# CVx1.net
KiCad netlist of a schematic drawn in Altium Designer
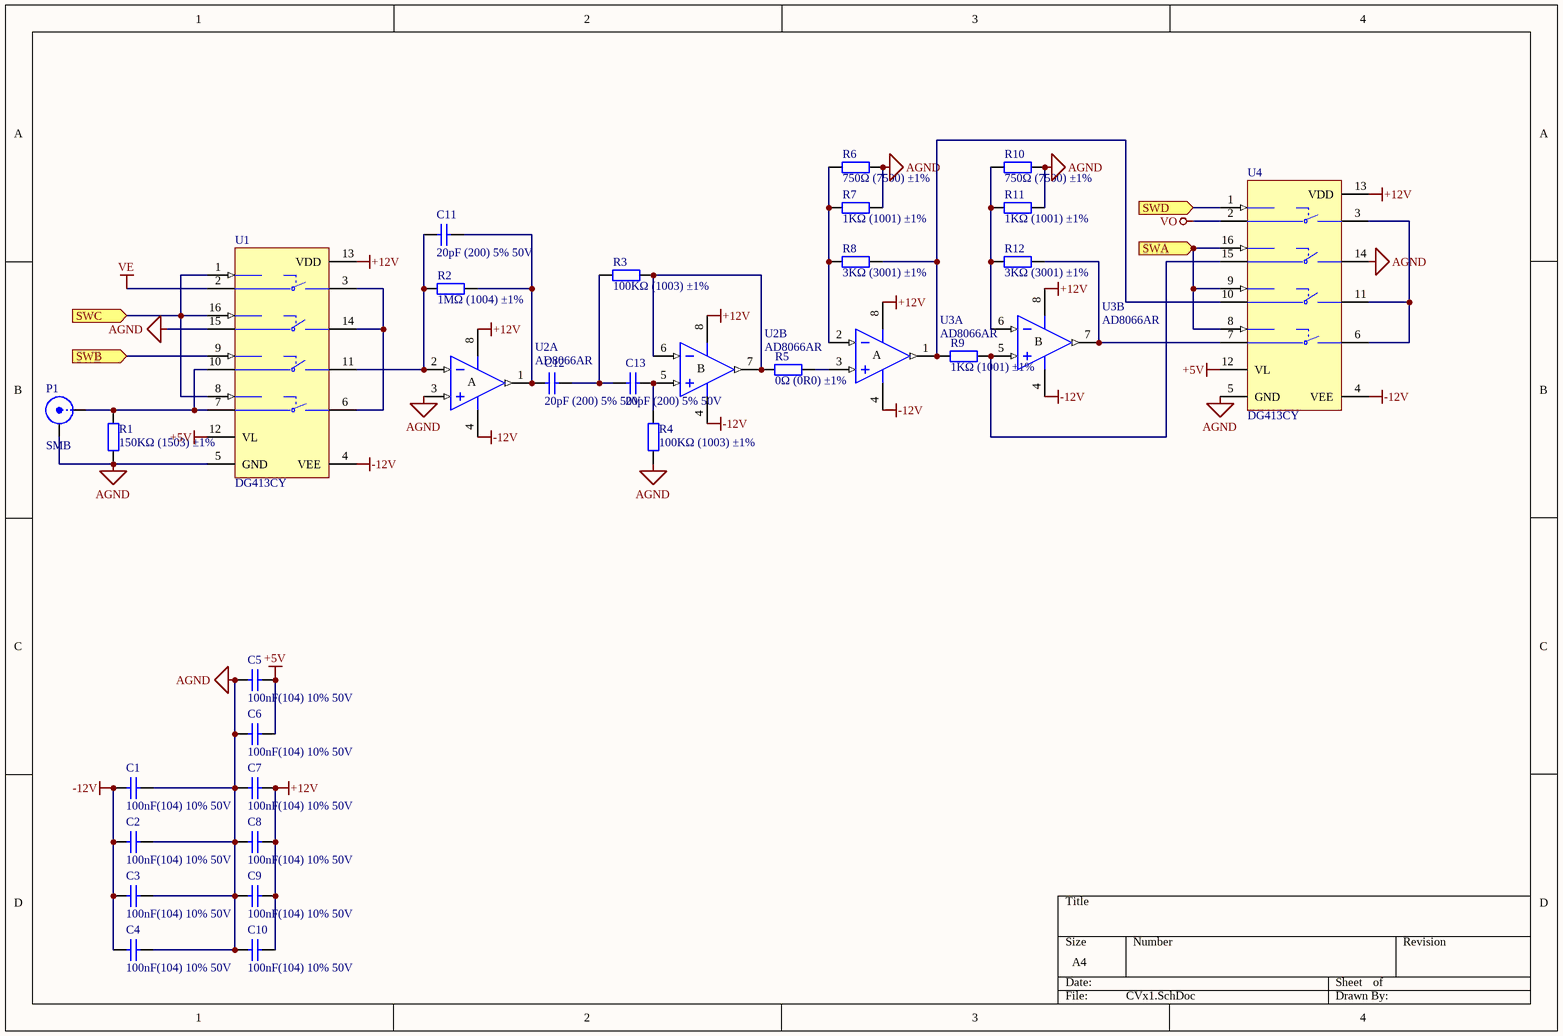
[diagram p0: CVx1.SchDoc]

(export (version "E")
  (design (tool "Eeschema 10.0.6"))
  (components
    (comp (ref "C1")
      (value "100nF(104) 10% 50V")
      (footprint "LC-0805_C")
      (description "贴片电容")
      (libsource (lib "Miscellaneous Devices LC") (part "0805 100nF(104) 10% 50V"))
    )
    (comp (ref "C2")
      (value "100nF(104) 10% 50V")
      (footprint "LC-0805_C")
      (description "贴片电容")
      (libsource (lib "Miscellaneous Devices LC") (part "0805 100nF(104) 10% 50V"))
    )
    (comp (ref "C3")
      (value "100nF(104) 10% 50V")
      (footprint "LC-0805_C")
      (description "贴片电容")
      (libsource (lib "Miscellaneous Devices LC") (part "0805 100nF(104) 10% 50V"))
    )
    (comp (ref "C4")
      (value "100nF(104) 10% 50V")
      (footprint "LC-0805_C")
      (description "贴片电容")
      (libsource (lib "Miscellaneous Devices LC") (part "0805 100nF(104) 10% 50V"))
    )
    (comp (ref "C5")
      (value "100nF(104) 10% 50V")
      (footprint "LC-0805_C")
      (description "贴片电容")
      (libsource (lib "Miscellaneous Devices LC") (part "0805 100nF(104) 10% 50V"))
    )
    (comp (ref "C6")
      (value "100nF(104) 10% 50V")
      (footprint "LC-0805_C")
      (description "贴片电容")
      (libsource (lib "Miscellaneous Devices LC") (part "0805 100nF(104) 10% 50V"))
    )
    (comp (ref "C7")
      (value "100nF(104) 10% 50V")
      (footprint "LC-0805_C")
      (description "贴片电容")
      (libsource (lib "Miscellaneous Devices LC") (part "0805 100nF(104) 10% 50V"))
    )
    (comp (ref "C8")
      (value "100nF(104) 10% 50V")
      (footprint "LC-0805_C")
      (description "贴片电容")
      (libsource (lib "Miscellaneous Devices LC") (part "0805 100nF(104) 10% 50V"))
    )
    (comp (ref "C9")
      (value "100nF(104) 10% 50V")
      (footprint "LC-0805_C")
      (description "贴片电容")
      (libsource (lib "Miscellaneous Devices LC") (part "0805 100nF(104) 10% 50V"))
    )
    (comp (ref "C10")
      (value "100nF(104) 10% 50V")
      (footprint "LC-0805_C")
      (description "贴片电容")
      (libsource (lib "Miscellaneous Devices LC") (part "0805 100nF(104) 10% 50V"))
    )
    (comp (ref "C11")
      (value "20pF (200) 5% 50V")
      (footprint "LC-0805_C")
      (description "贴片电容")
      (libsource (lib "Miscellaneous Devices LC") (part "0805 20pF (200) 5% 50V"))
    )
    (comp (ref "C12")
      (value "20pF (200) 5% 50V")
      (footprint "LC-0805_C")
      (description "贴片电容")
      (libsource (lib "Miscellaneous Devices LC") (part "0805 20pF (200) 5% 50V"))
    )
    (comp (ref "C13")
      (value "20pF (200) 5% 50V")
      (footprint "LC-0805_C")
      (description "贴片电容")
      (libsource (lib "Miscellaneous Devices LC") (part "0805 20pF (200) 5% 50V"))
    )
    (comp (ref "P1")
      (value "SMB")
      (footprint "SMB_V-RJ45")
      (description "SMB Straight Connector")
      (fields (field (name "PUBLISHER") "Altium Limited"))
      (libsource (lib "Miscellaneous Connectors") (part "SMB"))
    )
    (comp (ref "R1")
      (value "150KΩ (1503) ±1%")
      (footprint "LC-0805_R")
      (description "贴片电阻")
      (libsource (lib "Miscellaneous Devices LC") (part "0805 150KΩ (1503) 1%"))
    )
    (comp (ref "R2")
      (value "1MΩ (1004) ±1%")
      (footprint "LC-0805_R")
      (description "贴片电阻")
      (libsource (lib "Miscellaneous Devices LC") (part "0805 1MΩ (1004) 1%"))
    )
    (comp (ref "R3")
      (value "100KΩ (1003) ±1%")
      (footprint "LC-0805_R")
      (description "贴片电阻")
      (libsource (lib "Miscellaneous Devices LC") (part "0805 100KΩ (1003) 1%"))
    )
    (comp (ref "R4")
      (value "100KΩ (1003) ±1%")
      (footprint "LC-0805_R")
      (description "贴片电阻")
      (libsource (lib "") (part "0805 100KΩ (1003) 1%_1"))
    )
    (comp (ref "R5")
      (value "0Ω (0R0) ±1%")
      (footprint "LC-0805_R")
      (description "贴片电阻")
      (libsource (lib "Miscellaneous Devices LC") (part "0805 0Ω (0R0) 1%"))
    )
    (comp (ref "R6")
      (value "750Ω (7500) ±1%")
      (footprint "LC-0805_R")
      (description "贴片电阻")
      (libsource (lib "Miscellaneous Devices LC") (part "0805 750Ω (7500) 1%"))
    )
    (comp (ref "R7")
      (value "1KΩ (1001) ±1%")
      (footprint "LC-0805_R")
      (description "贴片电阻")
      (libsource (lib "Miscellaneous Devices LC") (part "0805 1KΩ (1001) 1%"))
    )
    (comp (ref "R8")
      (value "3KΩ (3001) ±1%")
      (footprint "LC-0805_R")
      (description "贴片电阻")
      (libsource (lib "Miscellaneous Devices LC") (part "0805 3KΩ (3001) 1%"))
    )
    (comp (ref "R9")
      (value "1KΩ (1001) ±1%")
      (footprint "LC-0805_R")
      (description "贴片电阻")
      (libsource (lib "Miscellaneous Devices LC") (part "0805 1KΩ (1001) 1%"))
    )
    (comp (ref "R10")
      (value "750Ω (7500) ±1%")
      (footprint "LC-0805_R")
      (description "贴片电阻")
      (libsource (lib "Miscellaneous Devices LC") (part "0805 750Ω (7500) 1%"))
    )
    (comp (ref "R11")
      (value "1KΩ (1001) ±1%")
      (footprint "LC-0805_R")
      (description "贴片电阻")
      (libsource (lib "Miscellaneous Devices LC") (part "0805 1KΩ (1001) 1%"))
    )
    (comp (ref "R12")
      (value "3KΩ (3001) ±1%")
      (footprint "LC-0805_R")
      (description "贴片电阻")
      (libsource (lib "Miscellaneous Devices LC") (part "0805 3KΩ (3001) 1%"))
    )
    (comp (ref "U1")
      (value "DG413CY")
      (footprint "NSO16_N")
      (description "Improved, Quad, SPST Analog Switches")
      (fields (field (name "PUBLISHER") "Altium Limited"))
      (libsource (lib "Maxim Logic Switch") (part "DG413CY"))
    )
    (comp (ref "U2")
      (value "AD8066AR")
      (footprint "SO-8_N")
      (description "Low Cost, 300MHz Voltage Feedback Amplifier")
      (fields (field (name "PUBLISHER") "Altium Limited"))
      (libsource (lib "AD Operational Amplifier") (part "AD8056AR"))
    )
    (comp (ref "U3")
      (value "AD8066AR")
      (footprint "SO-8_N")
      (description "Low Cost, 300MHz Voltage Feedback Amplifier")
      (fields (field (name "PUBLISHER") "Altium Limited"))
      (libsource (lib "AD Operational Amplifier") (part "AD8056AR"))
    )
    (comp (ref "U4")
      (value "DG413CY")
      (footprint "NSO16_N")
      (description "Improved, Quad, SPST Analog Switches")
      (fields (field (name "PUBLISHER") "Altium Limited"))
      (libsource (lib "Maxim Logic Switch") (part "DG413CY"))
    )
  )
  (nets
    (net (code "1") (name "+5V") (class "Default")
      (node (ref "C5") (pin "2") (pinfunction "2_2") (pintype "passive"))
      (node (ref "C6") (pin "2") (pinfunction "2_2") (pintype "passive"))
      (node (ref "U1") (pin "12") (pinfunction "VL_12") (pintype "power_in"))
      (node (ref "U4") (pin "12") (pinfunction "VL_12") (pintype "power_in"))
    )
    (net (code "2") (name "+12V") (class "Default")
      (node (ref "C10") (pin "2") (pinfunction "2_2") (pintype "passive"))
      (node (ref "C7") (pin "2") (pinfunction "2_2") (pintype "passive"))
      (node (ref "C8") (pin "2") (pinfunction "2_2") (pintype "passive"))
      (node (ref "C9") (pin "2") (pinfunction "2_2") (pintype "passive"))
      (node (ref "U1") (pin "13") (pinfunction "VDD_13") (pintype "power_in"))
      (node (ref "U2") (pin "8") (pinfunction "V+_8") (pintype "power_in"))
      (node (ref "U3") (pin "8") (pinfunction "V+_8") (pintype "power_in"))
      (node (ref "U4") (pin "13") (pinfunction "VDD_13") (pintype "power_in"))
    )
    (net (code "3") (name "-12V") (class "Default")
      (node (ref "C1") (pin "1") (pinfunction "1_1") (pintype "passive"))
      (node (ref "C2") (pin "1") (pinfunction "1_1") (pintype "passive"))
      (node (ref "C3") (pin "1") (pinfunction "1_1") (pintype "passive"))
      (node (ref "C4") (pin "1") (pinfunction "1_1") (pintype "passive"))
      (node (ref "U1") (pin "4") (pinfunction "VEE_4") (pintype "power_in"))
      (node (ref "U2") (pin "4") (pinfunction "V-_4") (pintype "power_in"))
      (node (ref "U3") (pin "4") (pinfunction "V-_4") (pintype "power_in"))
      (node (ref "U4") (pin "4") (pinfunction "VEE_4") (pintype "power_in"))
    )
    (net (code "4") (name "/SWA") (class "Default")
      (node (ref "U4") (pin "16") (pinfunction "IN2_16") (pintype "input"))
      (node (ref "U4") (pin "8") (pinfunction "IN_4_8") (pintype "input"))
      (node (ref "U4") (pin "9") (pinfunction "IN3_9") (pintype "input"))
    )
    (net (code "5") (name "/SWB") (class "Default")
      (node (ref "U1") (pin "9") (pinfunction "IN3_9") (pintype "input"))
    )
    (net (code "6") (name "/SWC") (class "Default")
      (node (ref "U1") (pin "1") (pinfunction "IN1_1") (pintype "input"))
      (node (ref "U1") (pin "16") (pinfunction "IN2_16") (pintype "input"))
      (node (ref "U1") (pin "8") (pinfunction "IN_4_8") (pintype "input"))
    )
    (net (code "7") (name "/SWD") (class "Default")
      (node (ref "U4") (pin "1") (pinfunction "IN1_1") (pintype "input"))
    )
    (net (code "8") (name "AGND") (class "Default")
      (node (ref "C1") (pin "2") (pinfunction "2_2") (pintype "passive"))
      (node (ref "C10") (pin "1") (pinfunction "1_1") (pintype "passive"))
      (node (ref "C2") (pin "2") (pinfunction "2_2") (pintype "passive"))
      (node (ref "C3") (pin "2") (pinfunction "2_2") (pintype "passive"))
      (node (ref "C4") (pin "2") (pinfunction "2_2") (pintype "passive"))
      (node (ref "C5") (pin "1") (pinfunction "1_1") (pintype "passive"))
      (node (ref "C6") (pin "1") (pinfunction "1_1") (pintype "passive"))
      (node (ref "C7") (pin "1") (pinfunction "1_1") (pintype "passive"))
      (node (ref "C8") (pin "1") (pinfunction "1_1") (pintype "passive"))
      (node (ref "C9") (pin "1") (pinfunction "1_1") (pintype "passive"))
      (node (ref "P1") (pin "2") (pinfunction "Y_2") (pintype "passive"))
      (node (ref "R1") (pin "2") (pinfunction "2_2") (pintype "passive"))
      (node (ref "R10") (pin "2") (pinfunction "2_2") (pintype "passive"))
      (node (ref "R11") (pin "2") (pinfunction "2_2") (pintype "passive"))
      (node (ref "R4") (pin "1") (pinfunction "1_1") (pintype "passive"))
      (node (ref "R6") (pin "2") (pinfunction "2_2") (pintype "passive"))
      (node (ref "R7") (pin "2") (pinfunction "2_2") (pintype "passive"))
      (node (ref "U1") (pin "15") (pinfunction "D2_15") (pintype "passive"))
      (node (ref "U1") (pin "5") (pinfunction "GND_5") (pintype "power_in"))
      (node (ref "U2") (pin "3") (pinfunction "IN+_3") (pintype "input"))
      (node (ref "U4") (pin "14") (pinfunction "S2_14") (pintype "passive"))
      (node (ref "U4") (pin "5") (pinfunction "GND_5") (pintype "power_in"))
    )
    (net (code "9") (name "Net-(C12-Pad2)") (class "Default")
      (node (ref "C12") (pin "2") (pinfunction "2_2") (pintype "passive"))
      (node (ref "C13") (pin "1") (pinfunction "1_1") (pintype "passive"))
      (node (ref "R3") (pin "2") (pinfunction "2_2") (pintype "passive"))
    )
    (net (code "10") (name "Net-(P1-X)") (class "Default")
      (node (ref "P1") (pin "1") (pinfunction "X_1") (pintype "passive"))
      (node (ref "R1") (pin "1") (pinfunction "1_1") (pintype "passive"))
      (node (ref "U1") (pin "10") (pinfunction "D3_10") (pintype "passive"))
      (node (ref "U1") (pin "7") (pinfunction "D4_7") (pintype "passive"))
    )
    (net (code "11") (name "Net-(U1-S1)") (class "Default")
      (node (ref "U1") (pin "14") (pinfunction "S2_14") (pintype "passive"))
      (node (ref "U1") (pin "3") (pinfunction "S1_3") (pintype "passive"))
      (node (ref "U1") (pin "6") (pinfunction "S4_6") (pintype "passive"))
    )
    (net (code "12") (name "Net-(U1-S3)") (class "Default")
      (node (ref "C11") (pin "1") (pinfunction "1_1") (pintype "passive"))
      (node (ref "R2") (pin "2") (pinfunction "2_2") (pintype "passive"))
      (node (ref "U1") (pin "11") (pinfunction "S3_11") (pintype "passive"))
      (node (ref "U2") (pin "2") (pinfunction "IN-_2") (pintype "input"))
    )
    (net (code "13") (name "Net-(U2A-OUT)") (class "Default")
      (node (ref "C11") (pin "2") (pinfunction "2_2") (pintype "passive"))
      (node (ref "C12") (pin "1") (pinfunction "1_1") (pintype "passive"))
      (node (ref "R2") (pin "1") (pinfunction "1_1") (pintype "passive"))
      (node (ref "U2") (pin "1") (pinfunction "OUT_1") (pintype "output"))
    )
    (net (code "14") (name "Net-(U2B-IN+)") (class "Default")
      (node (ref "C13") (pin "2") (pinfunction "2_2") (pintype "passive"))
      (node (ref "R4") (pin "2") (pinfunction "2_2") (pintype "passive"))
      (node (ref "U2") (pin "5") (pinfunction "IN+_5") (pintype "input"))
    )
    (net (code "15") (name "Net-(U2B-IN-)") (class "Default")
      (node (ref "R3") (pin "1") (pinfunction "1_1") (pintype "passive"))
      (node (ref "R5") (pin "1") (pinfunction "1_1") (pintype "passive"))
      (node (ref "U2") (pin "6") (pinfunction "IN-_6") (pintype "input"))
      (node (ref "U2") (pin "7") (pinfunction "OUT_7") (pintype "output"))
    )
    (net (code "16") (name "Net-(U3A-IN+)") (class "Default")
      (node (ref "R5") (pin "2") (pinfunction "2_2") (pintype "passive"))
      (node (ref "U3") (pin "3") (pinfunction "IN+_3") (pintype "input"))
    )
    (net (code "17") (name "Net-(U3A-IN-)") (class "Default")
      (node (ref "R6") (pin "1") (pinfunction "1_1") (pintype "passive"))
      (node (ref "R7") (pin "1") (pinfunction "1_1") (pintype "passive"))
      (node (ref "R8") (pin "1") (pinfunction "1_1") (pintype "passive"))
      (node (ref "U3") (pin "2") (pinfunction "IN-_2") (pintype "input"))
    )
    (net (code "18") (name "Net-(U3A-OUT)") (class "Default")
      (node (ref "R8") (pin "2") (pinfunction "2_2") (pintype "passive"))
      (node (ref "R9") (pin "1") (pinfunction "1_1") (pintype "passive"))
      (node (ref "U3") (pin "1") (pinfunction "OUT_1") (pintype "output"))
      (node (ref "U4") (pin "10") (pinfunction "D3_10") (pintype "passive"))
    )
    (net (code "19") (name "Net-(U3B-IN+)") (class "Default")
      (node (ref "R9") (pin "2") (pinfunction "2_2") (pintype "passive"))
      (node (ref "U3") (pin "5") (pinfunction "IN+_5") (pintype "input"))
      (node (ref "U4") (pin "15") (pinfunction "D2_15") (pintype "passive"))
    )
    (net (code "20") (name "Net-(U3B-IN-)") (class "Default")
      (node (ref "R10") (pin "1") (pinfunction "1_1") (pintype "passive"))
      (node (ref "R11") (pin "1") (pinfunction "1_1") (pintype "passive"))
      (node (ref "R12") (pin "1") (pinfunction "1_1") (pintype "passive"))
      (node (ref "U3") (pin "6") (pinfunction "IN-_6") (pintype "input"))
    )
    (net (code "21") (name "Net-(U3B-OUT)") (class "Default")
      (node (ref "R12") (pin "2") (pinfunction "2_2") (pintype "passive"))
      (node (ref "U3") (pin "7") (pinfunction "OUT_7") (pintype "output"))
      (node (ref "U4") (pin "7") (pinfunction "D4_7") (pintype "passive"))
    )
    (net (code "22") (name "Net-(U4-S1)") (class "Default")
      (node (ref "U4") (pin "11") (pinfunction "S3_11") (pintype "passive"))
      (node (ref "U4") (pin "3") (pinfunction "S1_3") (pintype "passive"))
      (node (ref "U4") (pin "6") (pinfunction "S4_6") (pintype "passive"))
    )
    (net (code "23") (name "VE") (class "Default")
      (node (ref "U1") (pin "2") (pinfunction "D1_2") (pintype "passive"))
    )
    (net (code "24") (name "VO") (class "Default")
      (node (ref "U4") (pin "2") (pinfunction "D1_2") (pintype "passive"))
    )
  )
)
